# Un_Bus.net
KiCad netlist of a schematic drawn in EAGLE
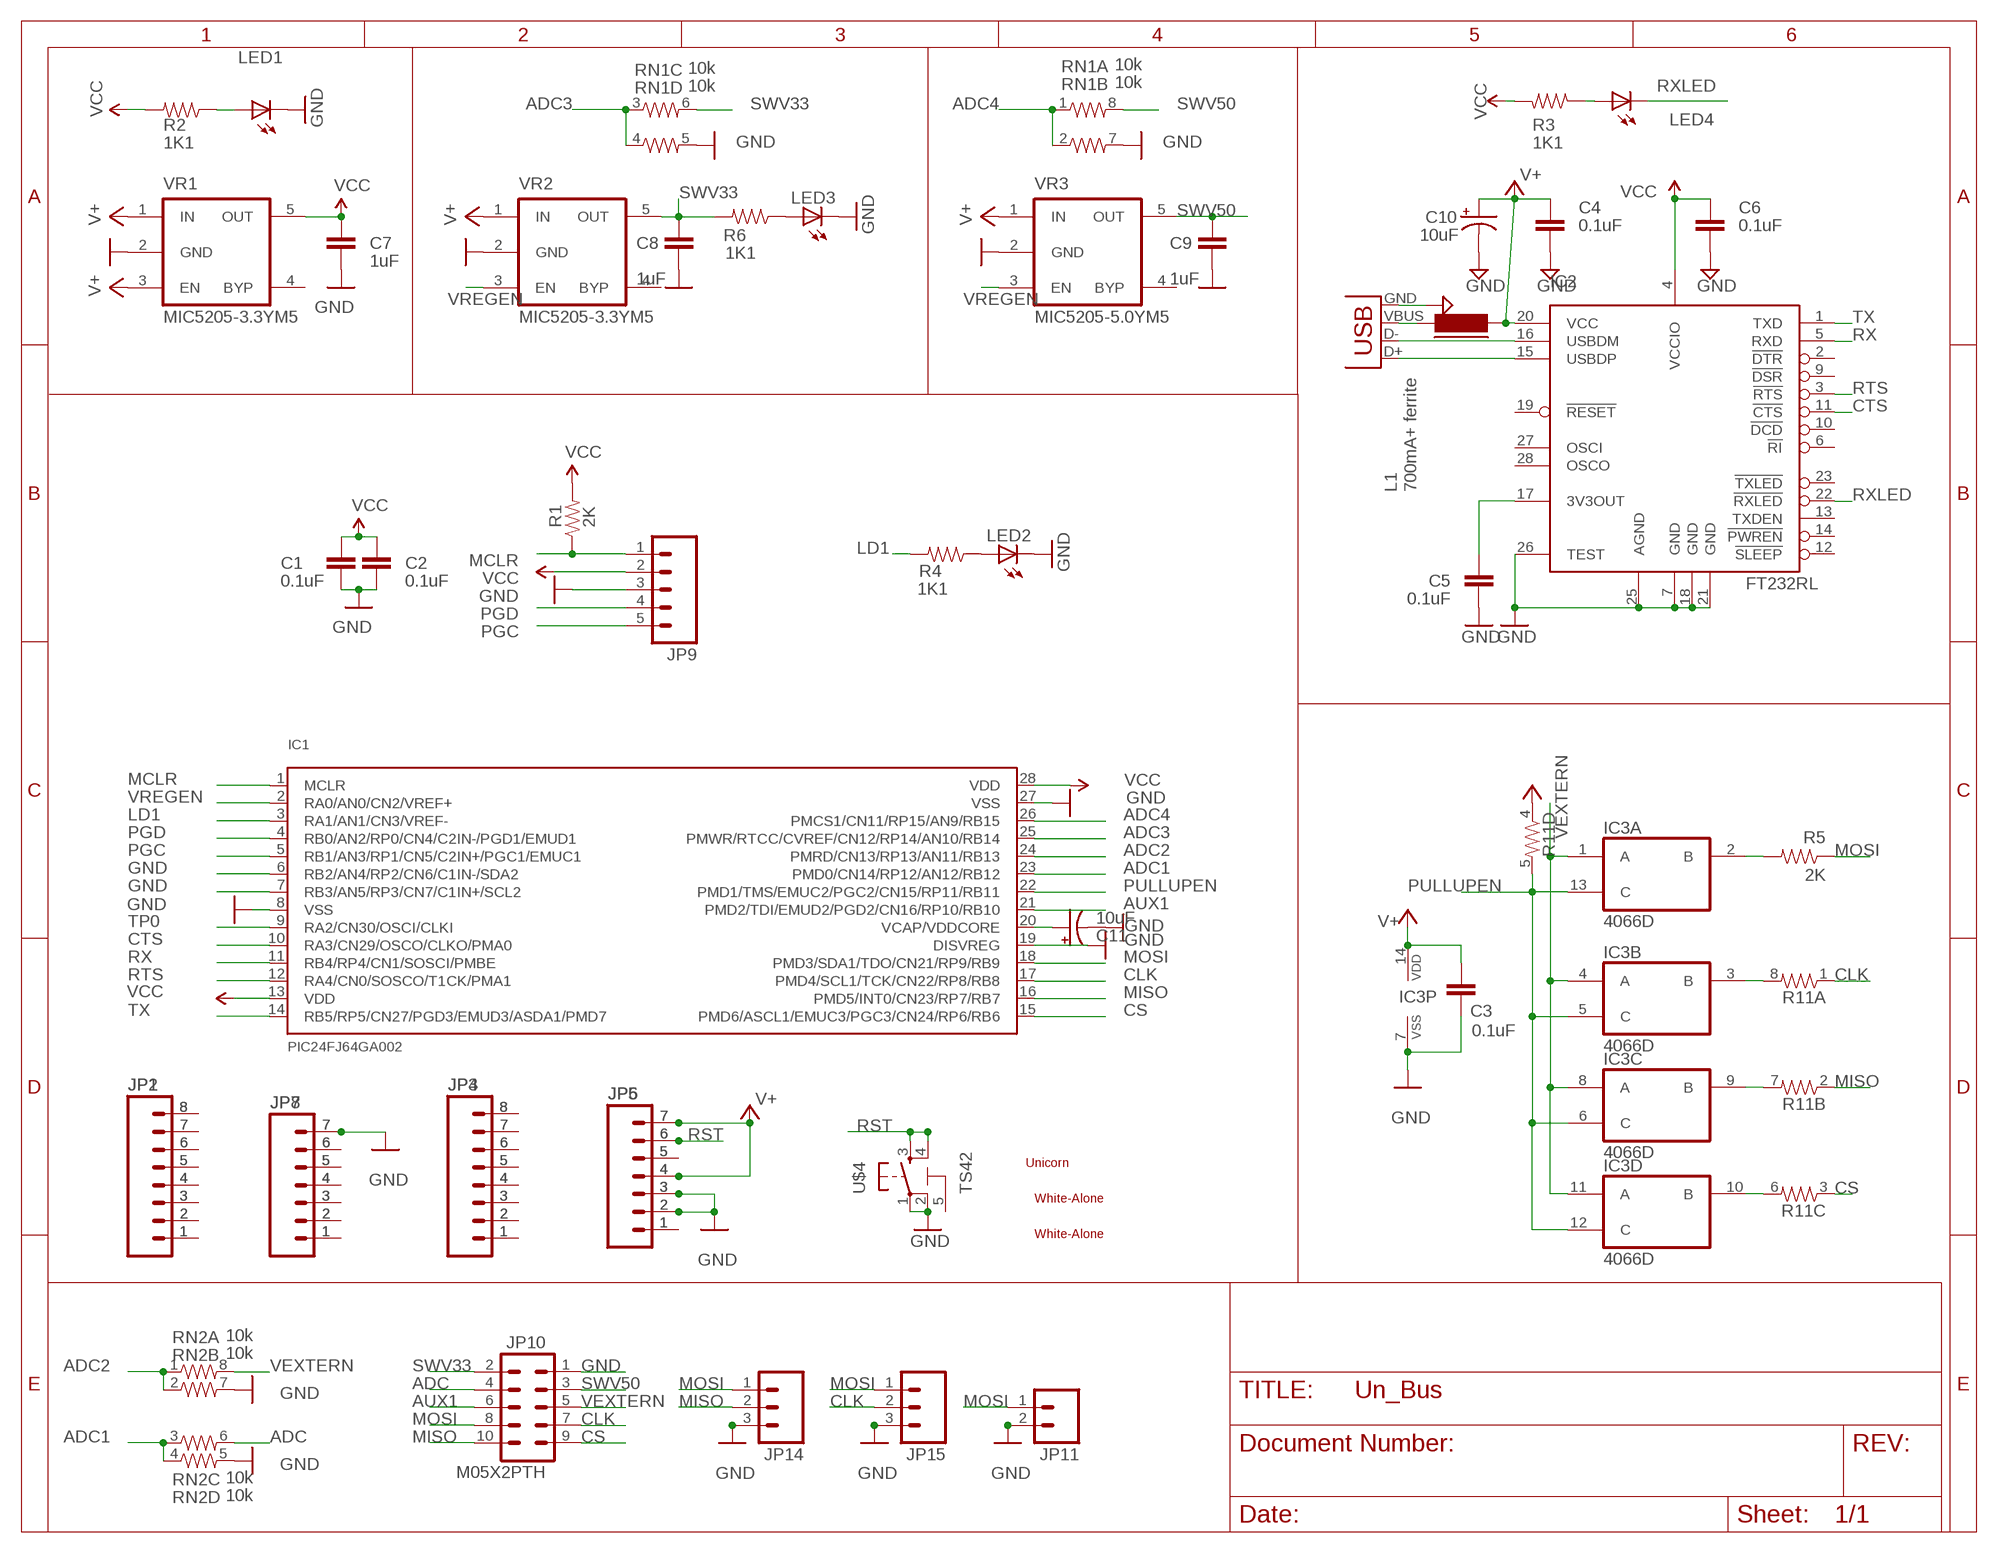
[diagram p0: schematic, sheet 1]

(export (version "E")
  (design (tool "Eeschema 10.0.6"))
  (components
    (comp (ref "C1")
      (value "0.1uF")
      (footprint "eagle-import:0603-CAP")
      (libsource (lib "eagle-import") (part "CAP0603-CAP"))
    )
    (comp (ref "C2")
      (value "0.1uF")
      (footprint "eagle-import:0603-CAP")
      (libsource (lib "eagle-import") (part "CAP0603-CAP"))
    )
    (comp (ref "C3")
      (value "0.1uF")
      (footprint "eagle-import:0603-CAP")
      (libsource (lib "eagle-import") (part "CAP0603-CAP"))
    )
    (comp (ref "C4")
      (value "0.1uF")
      (footprint "eagle-import:0603-CAP")
      (libsource (lib "eagle-import") (part "CAP0603-CAP"))
    )
    (comp (ref "C5")
      (value "0.1uF")
      (footprint "eagle-import:0603-CAP")
      (libsource (lib "eagle-import") (part "CAP0603-CAP"))
    )
    (comp (ref "C6")
      (value "0.1uF")
      (footprint "eagle-import:0603-CAP")
      (libsource (lib "eagle-import") (part "CAP0603-CAP"))
    )
    (comp (ref "C7")
      (value "1uF")
      (footprint "eagle-import:0603-CAP")
      (libsource (lib "eagle-import") (part "CAP0603-CAP"))
    )
    (comp (ref "C8")
      (value "1uF")
      (footprint "eagle-import:0603-CAP")
      (libsource (lib "eagle-import") (part "CAP0603-CAP"))
    )
    (comp (ref "C9")
      (value "1uF")
      (footprint "eagle-import:0603-CAP")
      (libsource (lib "eagle-import") (part "CAP0603-CAP"))
    )
    (comp (ref "C10")
      (value "10uF")
      (footprint "eagle-import:EIA3216")
      (libsource (lib "eagle-import") (part "CAP_POL1206"))
    )
    (comp (ref "C11")
      (value "10uF")
      (footprint "eagle-import:EIA3216")
      (libsource (lib "eagle-import") (part "CAP_POL1206"))
    )
    (comp (ref "IC1")
      (value "PIC24FJ64GA002")
      (footprint "eagle-import:SSOP28")
      (libsource (lib "eagle-import") (part "PIC24FJ64GA002"))
    )
    (comp (ref "IC2")
      (value "FT232RL")
      (footprint "eagle-import:SSOP28")
      (libsource (lib "eagle-import") (part "FT232RL"))
    )
    (comp (ref "IC3")
      (value "4066D")
      (footprint "eagle-import:SO14")
      (libsource (lib "eagle-import") (part "4066D"))
    )
    (comp (ref "JP1")
      (value "M081X08")
      (footprint "eagle-import:1X08")
      (libsource (lib "eagle-import") (part "M081X08"))
    )
    (comp (ref "JP2")
      (value "M081X08")
      (footprint "eagle-import:1X08")
      (libsource (lib "eagle-import") (part "M081X08"))
    )
    (comp (ref "JP3")
      (value "M081X08")
      (footprint "eagle-import:1X08")
      (libsource (lib "eagle-import") (part "M081X08"))
    )
    (comp (ref "JP4")
      (value "M081X08")
      (footprint "eagle-import:1X08")
      (libsource (lib "eagle-import") (part "M081X08"))
    )
    (comp (ref "JP5")
      (value "M07")
      (footprint "eagle-import:1X07")
      (libsource (lib "eagle-import") (part "M07"))
    )
    (comp (ref "JP6")
      (value "M07")
      (footprint "eagle-import:1X07")
      (libsource (lib "eagle-import") (part "M07"))
    )
    (comp (ref "JP7")
      (value "M07")
      (footprint "eagle-import:1X07")
      (libsource (lib "eagle-import") (part "M07"))
    )
    (comp (ref "JP8")
      (value "M07")
      (footprint "eagle-import:1X07")
      (libsource (lib "eagle-import") (part "M07"))
    )
    (comp (ref "JP9")
      (value "M05PTH")
      (footprint "eagle-import:1X05")
      (libsource (lib "eagle-import") (part "M05PTH"))
    )
    (comp (ref "JP10")
      (value "M05X2PTH")
      (footprint "eagle-import:AVR_ICSP")
      (libsource (lib "eagle-import") (part "M05X2PTH"))
    )
    (comp (ref "JP11")
      (value "M02PTH")
      (footprint "eagle-import:1X02")
      (libsource (lib "eagle-import") (part "M02PTH"))
    )
    (comp (ref "JP14")
      (value "M03PTH")
      (footprint "eagle-import:1X03")
      (libsource (lib "eagle-import") (part "M03PTH"))
    )
    (comp (ref "JP15")
      (value "M03PTH")
      (footprint "eagle-import:1X03")
      (libsource (lib "eagle-import") (part "M03PTH"))
    )
    (comp (ref "L1")
      (value "700mA+ ferrite")
      (footprint "eagle-import:FB805")
      (libsource (lib "eagle-import") (part "FERRITE-0805"))
    )
    (comp (ref "LED1")
      (value "LED0805")
      (footprint "eagle-import:LED-0805")
      (libsource (lib "eagle-import") (part "LED0805"))
    )
    (comp (ref "LED2")
      (value "LED0805")
      (footprint "eagle-import:LED-0805")
      (libsource (lib "eagle-import") (part "LED0805"))
    )
    (comp (ref "LED3")
      (value "LED0805")
      (footprint "eagle-import:LED-0805")
      (libsource (lib "eagle-import") (part "LED0805"))
    )
    (comp (ref "LED4")
      (value "LED0805")
      (footprint "eagle-import:LED-0805")
      (libsource (lib "eagle-import") (part "LED0805"))
    )
    (comp (ref "R1")
      (value "2K")
      (footprint "eagle-import:0603-RES")
      (libsource (lib "eagle-import") (part "2SparkFun_RESISTOR0603-RES"))
    )
    (comp (ref "R2")
      (value "1K1")
      (footprint "eagle-import:0603-RES")
      (libsource (lib "eagle-import") (part "RESISTOR0603-RES"))
    )
    (comp (ref "R3")
      (value "1K1")
      (footprint "eagle-import:0603-RES")
      (libsource (lib "eagle-import") (part "RESISTOR0603-RES"))
    )
    (comp (ref "R4")
      (value "1K1")
      (footprint "eagle-import:0603-RES")
      (libsource (lib "eagle-import") (part "RESISTOR0603-RES"))
    )
    (comp (ref "R5")
      (value "2K")
      (footprint "eagle-import:0603-RES")
      (libsource (lib "eagle-import") (part "2SparkFun_RESISTOR0603-RES"))
    )
    (comp (ref "R6")
      (value "1K1")
      (footprint "eagle-import:0603-RES")
      (libsource (lib "eagle-import") (part "RESISTOR0603-RES"))
    )
    (comp (ref "R11")
      (value "RESISTOR-ARRAY")
      (footprint "eagle-import:RES-NET-0603")
      (libsource (lib "eagle-import") (part "RESISTOR-ARRAY"))
    )
    (comp (ref "RN1")
      (value "10k")
      (footprint "eagle-import:RES-NET-0603")
      (libsource (lib "eagle-import") (part "RESISTOR-ARRAY"))
    )
    (comp (ref "RN2")
      (value "10k")
      (footprint "eagle-import:RES-NET-0603")
      (libsource (lib "eagle-import") (part "RESISTOR-ARRAY"))
    )
    (comp (ref "U$1")
      (value "UNICORN")
      (footprint "eagle-import:UNICORN_1")
      (libsource (lib "eagle-import") (part "UNICORN"))
    )
    (comp (ref "U$2")
      (value "WHITE-ALONE_0")
      (footprint "eagle-import:WHITE-ALONE_0")
      (libsource (lib "eagle-import") (part "WHITE-ALONE_0"))
    )
    (comp (ref "U$3")
      (value "WHITE-ALONE_0")
      (footprint "eagle-import:WHITE-ALONE_0")
      (libsource (lib "eagle-import") (part "WHITE-ALONE_0"))
    )
    (comp (ref "U$4")
      (value "TS42")
      (footprint "eagle-import:TS42")
      (libsource (lib "eagle-import") (part "TS42"))
    )
    (comp (ref "VR1")
      (value "MIC5205-3.3YM5")
      (footprint "eagle-import:SOT-23-5")
      (libsource (lib "eagle-import") (part "MIC5205"))
    )
    (comp (ref "VR2")
      (value "MIC5205-3.3YM5")
      (footprint "eagle-import:SOT-23-5")
      (libsource (lib "eagle-import") (part "MIC5205"))
    )
    (comp (ref "VR3")
      (value "MIC5205-5.0YM5")
      (footprint "eagle-import:SOT-23-5")
      (libsource (lib "eagle-import") (part "MIC5205"))
    )
    (comp (ref "X1")
      (value "USBSMD")
      (footprint "eagle-import:USB-MINIB")
      (libsource (lib "eagle-import") (part "USBSMD"))
    )
  )
  (nets
    (net (code "1") (name "/ADC") (class "Default")
      (node (ref "JP10") (pin "4") (pinfunction "4_4") (pintype "passive"))
      (node (ref "RN2") (pin "6") (pinfunction "2_6") (pintype "passive"))
    )
    (net (code "2") (name "/ADC1") (class "Default")
      (node (ref "IC1") (pin "23") (pinfunction "PMD0/CN14/RP12/AN12/RB12_23") (pintype "bidirectional"))
      (node (ref "RN2") (pin "3") (pinfunction "1_3") (pintype "passive"))
      (node (ref "RN2") (pin "4") (pinfunction "1_4") (pintype "passive"))
    )
    (net (code "3") (name "/ADC2") (class "Default")
      (node (ref "IC1") (pin "24") (pinfunction "PMRD/CN13/RP13/AN11/RB13_24") (pintype "bidirectional"))
      (node (ref "RN2") (pin "1") (pinfunction "1_1") (pintype "passive"))
      (node (ref "RN2") (pin "2") (pinfunction "1_2") (pintype "passive"))
    )
    (net (code "4") (name "/ADC3") (class "Default")
      (node (ref "IC1") (pin "25") (pinfunction "PMWR/RTCC/CVREF/CN12/RP14/AN10/RB14_25") (pintype "bidirectional"))
      (node (ref "RN1") (pin "3") (pinfunction "1_3") (pintype "passive"))
      (node (ref "RN1") (pin "4") (pinfunction "1_4") (pintype "passive"))
    )
    (net (code "5") (name "/ADC4") (class "Default")
      (node (ref "IC1") (pin "26") (pinfunction "PMCS1/CN11/RP15/AN9/RB15_26") (pintype "bidirectional"))
      (node (ref "RN1") (pin "1") (pinfunction "1_1") (pintype "passive"))
      (node (ref "RN1") (pin "2") (pinfunction "1_2") (pintype "passive"))
    )
    (net (code "6") (name "/AUX1") (class "Default")
      (node (ref "IC1") (pin "21") (pinfunction "PMD2/TDI/EMUD2/PGD2/CN16/RP10/RB10_21") (pintype "bidirectional"))
      (node (ref "JP10") (pin "6") (pinfunction "6_6") (pintype "passive"))
    )
    (net (code "7") (name "/CLK") (class "Default")
      (node (ref "IC1") (pin "17") (pinfunction "PMD4/SCL1/TCK/CN22/RP8/RB8_17") (pintype "bidirectional"))
      (node (ref "JP10") (pin "7") (pinfunction "7_7") (pintype "passive"))
      (node (ref "JP15") (pin "2") (pinfunction "2_2") (pintype "passive"))
      (node (ref "R11") (pin "1") (pinfunction "1_1") (pintype "passive"))
    )
    (net (code "8") (name "/CS") (class "Default")
      (node (ref "IC1") (pin "15") (pinfunction "PMD6/ASCL1/EMUC3/PGC3/CN24/RP6/RB6_15") (pintype "bidirectional"))
      (node (ref "JP10") (pin "9") (pinfunction "9_9") (pintype "passive"))
      (node (ref "R11") (pin "3") (pinfunction "1_3") (pintype "passive"))
    )
    (net (code "9") (name "/CTS") (class "Default")
      (node (ref "IC1") (pin "10") (pinfunction "RA3/CN29/OSCO/CLKO/PMA0_10") (pintype "bidirectional"))
      (node (ref "IC2") (pin "11") (pinfunction "~{CTS}_11") (pintype "bidirectional"))
    )
    (net (code "10") (name "/LD1") (class "Default")
      (node (ref "IC1") (pin "3") (pinfunction "RA1/AN1/CN3/VREF-_3") (pintype "bidirectional"))
      (node (ref "R4") (pin "2") (pinfunction "2_2") (pintype "passive"))
    )
    (net (code "11") (name "/MCLR") (class "Default")
      (node (ref "IC1") (pin "1") (pinfunction "MCLR_1") (pintype "input"))
      (node (ref "JP9") (pin "1") (pinfunction "1_1") (pintype "passive"))
      (node (ref "R1") (pin "1") (pinfunction "1_1") (pintype "passive"))
    )
    (net (code "12") (name "/MISO") (class "Default")
      (node (ref "IC1") (pin "16") (pinfunction "PMD5/INT0/CN23/RP7/RB7_16") (pintype "bidirectional"))
      (node (ref "JP10") (pin "10") (pinfunction "10_10") (pintype "passive"))
      (node (ref "JP14") (pin "2") (pinfunction "2_2") (pintype "passive"))
      (node (ref "R11") (pin "2") (pinfunction "1_2") (pintype "passive"))
    )
    (net (code "13") (name "/MOSI") (class "Default")
      (node (ref "IC1") (pin "18") (pinfunction "PMD3/SDA1/TDO/CN21/RP9/RB9_18") (pintype "bidirectional"))
      (node (ref "JP10") (pin "8") (pinfunction "8_8") (pintype "passive"))
      (node (ref "JP11") (pin "1") (pinfunction "1_1") (pintype "passive"))
      (node (ref "JP14") (pin "1") (pinfunction "1_1") (pintype "passive"))
      (node (ref "JP15") (pin "1") (pinfunction "1_1") (pintype "passive"))
      (node (ref "R5") (pin "1") (pinfunction "1_1") (pintype "passive"))
    )
    (net (code "14") (name "/PGC") (class "Default")
      (node (ref "IC1") (pin "5") (pinfunction "RB1/AN3/RP1/CN5/C2IN+/PGC1/EMUC1_5") (pintype "bidirectional"))
      (node (ref "JP9") (pin "5") (pinfunction "5_5") (pintype "passive"))
    )
    (net (code "15") (name "/PGD") (class "Default")
      (node (ref "IC1") (pin "4") (pinfunction "RB0/AN2/RP0/CN4/C2IN-/PGD1/EMUD1_4") (pintype "bidirectional"))
      (node (ref "JP9") (pin "4") (pinfunction "4_4") (pintype "passive"))
    )
    (net (code "16") (name "/PULLUPEN") (class "Default")
      (node (ref "IC1") (pin "22") (pinfunction "PMD1/TMS/EMUC2/PGC2/CN15/RP11/RB11_22") (pintype "bidirectional"))
      (node (ref "IC3") (pin "12") (pinfunction "C_12") (pintype "input"))
      (node (ref "IC3") (pin "13") (pinfunction "C_13") (pintype "input"))
      (node (ref "IC3") (pin "5") (pinfunction "C_5") (pintype "input"))
      (node (ref "IC3") (pin "6") (pinfunction "C_6") (pintype "input"))
      (node (ref "R11") (pin "5") (pinfunction "2_5") (pintype "passive"))
    )
    (net (code "17") (name "/RST") (class "Default")
      (node (ref "JP5") (pin "6") (pinfunction "6_6") (pintype "passive"))
      (node (ref "JP6") (pin "6") (pinfunction "6_6") (pintype "passive"))
      (node (ref "U$4") (pin "3") (pinfunction "3_3") (pintype "passive"))
      (node (ref "U$4") (pin "4") (pinfunction "4_4") (pintype "passive"))
    )
    (net (code "18") (name "/RTS") (class "Default")
      (node (ref "IC1") (pin "12") (pinfunction "RA4/CN0/SOSCO/T1CK/PMA1_12") (pintype "bidirectional"))
      (node (ref "IC2") (pin "3") (pinfunction "~{RTS}_3") (pintype "bidirectional"))
    )
    (net (code "19") (name "/RX") (class "Default")
      (node (ref "IC1") (pin "11") (pinfunction "RB4/RP4/CN1/SOSCI/PMBE_11") (pintype "bidirectional"))
      (node (ref "IC2") (pin "5") (pinfunction "RXD_5") (pintype "bidirectional"))
    )
    (net (code "20") (name "/RXLED") (class "Default")
      (node (ref "IC2") (pin "22") (pinfunction "~{RXLED}_22") (pintype "bidirectional"))
      (node (ref "LED4") (pin "2") (pinfunction "C_2") (pintype "passive"))
    )
    (net (code "21") (name "/SWV33") (class "Default")
      (node (ref "C8") (pin "1") (pinfunction "1_1") (pintype "passive"))
      (node (ref "JP10") (pin "2") (pinfunction "2_2") (pintype "passive"))
      (node (ref "R6") (pin "2") (pinfunction "2_2") (pintype "passive"))
      (node (ref "RN1") (pin "6") (pinfunction "2_6") (pintype "passive"))
      (node (ref "VR2") (pin "5") (pinfunction "OUT_5") (pintype "bidirectional"))
    )
    (net (code "22") (name "/SWV50") (class "Default")
      (node (ref "C9") (pin "1") (pinfunction "1_1") (pintype "passive"))
      (node (ref "JP10") (pin "3") (pinfunction "3_3") (pintype "passive"))
      (node (ref "RN1") (pin "8") (pinfunction "2_8") (pintype "passive"))
      (node (ref "VR3") (pin "5") (pinfunction "OUT_5") (pintype "bidirectional"))
    )
    (net (code "23") (name "/TP0") (class "Default")
      (node (ref "IC1") (pin "9") (pinfunction "RA2/CN30/OSCI/CLKI_9") (pintype "bidirectional"))
    )
    (net (code "24") (name "/TX") (class "Default")
      (node (ref "IC1") (pin "14") (pinfunction "RB5/RP5/CN27/PGD3/EMUD3/ASDA1/PMD7_14") (pintype "bidirectional"))
      (node (ref "IC2") (pin "1") (pinfunction "TXD_1") (pintype "bidirectional"))
    )
    (net (code "25") (name "/VEXTERN") (class "Default")
      (node (ref "IC3") (pin "1") (pinfunction "A_1") (pintype "tri_state"))
      (node (ref "IC3") (pin "11") (pinfunction "A_11") (pintype "tri_state"))
      (node (ref "IC3") (pin "4") (pinfunction "A_4") (pintype "tri_state"))
      (node (ref "IC3") (pin "8") (pinfunction "A_8") (pintype "tri_state"))
      (node (ref "JP10") (pin "5") (pinfunction "5_5") (pintype "passive"))
      (node (ref "RN2") (pin "8") (pinfunction "2_8") (pintype "passive"))
    )
    (net (code "26") (name "/VREGEN") (class "Default")
      (node (ref "IC1") (pin "2") (pinfunction "RA0/AN0/CN2/VREF+_2") (pintype "bidirectional"))
      (node (ref "VR2") (pin "3") (pinfunction "EN_3") (pintype "bidirectional"))
      (node (ref "VR3") (pin "3") (pinfunction "EN_3") (pintype "bidirectional"))
    )
    (net (code "27") (name "GND") (class "Default")
      (node (ref "C1") (pin "2") (pinfunction "2_2") (pintype "passive"))
      (node (ref "C10") (pin "C") (pinfunction "-_C") (pintype "passive"))
      (node (ref "C11") (pin "C") (pinfunction "-_C") (pintype "passive"))
      (node (ref "C2") (pin "2") (pinfunction "2_2") (pintype "passive"))
      (node (ref "C3") (pin "2") (pinfunction "2_2") (pintype "passive"))
      (node (ref "C4") (pin "2") (pinfunction "2_2") (pintype "passive"))
      (node (ref "C5") (pin "2") (pinfunction "2_2") (pintype "passive"))
      (node (ref "C6") (pin "2") (pinfunction "2_2") (pintype "passive"))
      (node (ref "C7") (pin "2") (pinfunction "2_2") (pintype "passive"))
      (node (ref "C8") (pin "2") (pinfunction "2_2") (pintype "passive"))
      (node (ref "C9") (pin "2") (pinfunction "2_2") (pintype "passive"))
      (node (ref "IC1") (pin "19") (pinfunction "DISVREG_19") (pintype "power_in"))
      (node (ref "IC1") (pin "27") (pinfunction "VSS_27") (pintype "power_in"))
      (node (ref "IC1") (pin "6") (pinfunction "RB2/AN4/RP2/CN6/C1IN-/SDA2_6") (pintype "bidirectional"))
      (node (ref "IC1") (pin "7") (pinfunction "RB3/AN5/RP3/CN7/C1IN+/SCL2_7") (pintype "bidirectional"))
      (node (ref "IC1") (pin "8") (pinfunction "VSS_8") (pintype "power_in"))
      (node (ref "IC2") (pin "18") (pinfunction "GND_18") (pintype "bidirectional"))
      (node (ref "IC2") (pin "21") (pinfunction "GND_21") (pintype "bidirectional"))
      (node (ref "IC2") (pin "25") (pinfunction "AGND_25") (pintype "bidirectional"))
      (node (ref "IC2") (pin "26") (pinfunction "TEST_26") (pintype "bidirectional"))
      (node (ref "IC2") (pin "7") (pinfunction "GND_7") (pintype "bidirectional"))
      (node (ref "IC3") (pin "7") (pinfunction "VSS_7") (pintype "power_in"))
      (node (ref "JP10") (pin "1") (pinfunction "1_1") (pintype "passive"))
      (node (ref "JP11") (pin "2") (pinfunction "2_2") (pintype "passive"))
      (node (ref "JP14") (pin "3") (pinfunction "3_3") (pintype "passive"))
      (node (ref "JP15") (pin "3") (pinfunction "3_3") (pintype "passive"))
      (node (ref "JP5") (pin "2") (pinfunction "2_2") (pintype "passive"))
      (node (ref "JP5") (pin "3") (pinfunction "3_3") (pintype "passive"))
      (node (ref "JP6") (pin "2") (pinfunction "2_2") (pintype "passive"))
      (node (ref "JP6") (pin "3") (pinfunction "3_3") (pintype "passive"))
      (node (ref "JP7") (pin "7") (pinfunction "7_7") (pintype "passive"))
      (node (ref "JP8") (pin "7") (pinfunction "7_7") (pintype "passive"))
      (node (ref "JP9") (pin "3") (pinfunction "3_3") (pintype "passive"))
      (node (ref "LED1") (pin "2") (pinfunction "C_2") (pintype "passive"))
      (node (ref "LED2") (pin "2") (pinfunction "C_2") (pintype "passive"))
      (node (ref "LED3") (pin "2") (pinfunction "C_2") (pintype "passive"))
      (node (ref "RN1") (pin "5") (pinfunction "2_5") (pintype "passive"))
      (node (ref "RN1") (pin "7") (pinfunction "2_7") (pintype "passive"))
      (node (ref "RN2") (pin "5") (pinfunction "2_5") (pintype "passive"))
      (node (ref "RN2") (pin "7") (pinfunction "2_7") (pintype "passive"))
      (node (ref "U$4") (pin "1") (pinfunction "1_1") (pintype "passive"))
      (node (ref "U$4") (pin "2") (pinfunction "2_2") (pintype "passive"))
      (node (ref "VR1") (pin "2") (pinfunction "GND_2") (pintype "bidirectional"))
      (node (ref "VR2") (pin "2") (pinfunction "GND_2") (pintype "bidirectional"))
      (node (ref "VR3") (pin "2") (pinfunction "GND_2") (pintype "bidirectional"))
      (node (ref "X1") (pin "GND") (pinfunction "GND_GND") (pintype "bidirectional"))
    )
    (net (code "28") (name "Net-(C11-+)") (class "Default")
      (node (ref "C11") (pin "A") (pinfunction "+_A") (pintype "passive"))
      (node (ref "IC1") (pin "20") (pinfunction "VCAP/VDDCORE_20") (pintype "power_in"))
    )
    (net (code "29") (name "Net-(IC2-3V3OUT)") (class "Default")
      (node (ref "C5") (pin "1") (pinfunction "1_1") (pintype "passive"))
      (node (ref "IC2") (pin "17") (pinfunction "3V3OUT_17") (pintype "bidirectional"))
    )
    (net (code "30") (name "Net-(IC2-USBDM)") (class "Default")
      (node (ref "IC2") (pin "16") (pinfunction "USBDM_16") (pintype "bidirectional"))
      (node (ref "X1") (pin "D-") (pinfunction "D-_D-") (pintype "bidirectional"))
    )
    (net (code "31") (name "Net-(IC2-USBDP)") (class "Default")
      (node (ref "IC2") (pin "15") (pinfunction "USBDP_15") (pintype "bidirectional"))
      (node (ref "X1") (pin "D+") (pinfunction "D+_D+") (pintype "bidirectional"))
    )
    (net (code "32") (name "Net-(IC3A-B)") (class "Default")
      (node (ref "IC3") (pin "2") (pinfunction "B_2") (pintype "tri_state"))
      (node (ref "R5") (pin "2") (pinfunction "2_2") (pintype "passive"))
    )
    (net (code "33") (name "Net-(IC3B-B)") (class "Default")
      (node (ref "IC3") (pin "3") (pinfunction "B_3") (pintype "tri_state"))
      (node (ref "R11") (pin "8") (pinfunction "2_8") (pintype "passive"))
    )
    (net (code "34") (name "Net-(IC3C-B)") (class "Default")
      (node (ref "IC3") (pin "9") (pinfunction "B_9") (pintype "tri_state"))
      (node (ref "R11") (pin "7") (pinfunction "2_7") (pintype "passive"))
    )
    (net (code "35") (name "Net-(IC3D-B)") (class "Default")
      (node (ref "IC3") (pin "10") (pinfunction "B_10") (pintype "tri_state"))
      (node (ref "R11") (pin "6") (pinfunction "2_6") (pintype "passive"))
    )
    (net (code "36") (name "Net-(JP1-Pad1)") (class "Default")
      (node (ref "JP1") (pin "1") (pinfunction "1_1") (pintype "passive"))
      (node (ref "JP2") (pin "1") (pinfunction "1_1") (pintype "passive"))
    )
    (net (code "37") (name "Net-(JP1-Pad2)") (class "Default")
      (node (ref "JP1") (pin "2") (pinfunction "2_2") (pintype "passive"))
      (node (ref "JP2") (pin "2") (pinfunction "2_2") (pintype "passive"))
    )
    (net (code "38") (name "Net-(JP1-Pad3)") (class "Default")
      (node (ref "JP1") (pin "3") (pinfunction "3_3") (pintype "passive"))
      (node (ref "JP2") (pin "3") (pinfunction "3_3") (pintype "passive"))
    )
    (net (code "39") (name "Net-(JP1-Pad4)") (class "Default")
      (node (ref "JP1") (pin "4") (pinfunction "4_4") (pintype "passive"))
      (node (ref "JP2") (pin "4") (pinfunction "4_4") (pintype "passive"))
    )
    (net (code "40") (name "Net-(JP1-Pad5)") (class "Default")
      (node (ref "JP1") (pin "5") (pinfunction "5_5") (pintype "passive"))
      (node (ref "JP2") (pin "5") (pinfunction "5_5") (pintype "passive"))
    )
    (net (code "41") (name "Net-(JP1-Pad6)") (class "Default")
      (node (ref "JP1") (pin "6") (pinfunction "6_6") (pintype "passive"))
      (node (ref "JP2") (pin "6") (pinfunction "6_6") (pintype "passive"))
    )
    (net (code "42") (name "Net-(JP1-Pad7)") (class "Default")
      (node (ref "JP1") (pin "7") (pinfunction "7_7") (pintype "passive"))
      (node (ref "JP2") (pin "7") (pinfunction "7_7") (pintype "passive"))
    )
    (net (code "43") (name "Net-(JP1-Pad8)") (class "Default")
      (node (ref "JP1") (pin "8") (pinfunction "8_8") (pintype "passive"))
      (node (ref "JP2") (pin "8") (pinfunction "8_8") (pintype "passive"))
    )
    (net (code "44") (name "Net-(JP3-Pad1)") (class "Default")
      (node (ref "JP3") (pin "1") (pinfunction "1_1") (pintype "passive"))
      (node (ref "JP4") (pin "1") (pinfunction "1_1") (pintype "passive"))
    )
    (net (code "45") (name "Net-(JP3-Pad2)") (class "Default")
      (node (ref "JP3") (pin "2") (pinfunction "2_2") (pintype "passive"))
      (node (ref "JP4") (pin "2") (pinfunction "2_2") (pintype "passive"))
    )
    (net (code "46") (name "Net-(JP3-Pad3)") (class "Default")
      (node (ref "JP3") (pin "3") (pinfunction "3_3") (pintype "passive"))
      (node (ref "JP4") (pin "3") (pinfunction "3_3") (pintype "passive"))
    )
    (net (code "47") (name "Net-(JP3-Pad4)") (class "Default")
      (node (ref "JP3") (pin "4") (pinfunction "4_4") (pintype "passive"))
      (node (ref "JP4") (pin "4") (pinfunction "4_4") (pintype "passive"))
    )
    (net (code "48") (name "Net-(JP3-Pad5)") (class "Default")
      (node (ref "JP3") (pin "5") (pinfunction "5_5") (pintype "passive"))
      (node (ref "JP4") (pin "5") (pinfunction "5_5") (pintype "passive"))
    )
    (net (code "49") (name "Net-(JP3-Pad6)") (class "Default")
      (node (ref "JP3") (pin "6") (pinfunction "6_6") (pintype "passive"))
      (node (ref "JP4") (pin "6") (pinfunction "6_6") (pintype "passive"))
    )
    (net (code "50") (name "Net-(JP3-Pad7)") (class "Default")
      (node (ref "JP3") (pin "7") (pinfunction "7_7") (pintype "passive"))
      (node (ref "JP4") (pin "7") (pinfunction "7_7") (pintype "passive"))
    )
    (net (code "51") (name "Net-(JP3-Pad8)") (class "Default")
      (node (ref "JP3") (pin "8") (pinfunction "8_8") (pintype "passive"))
      (node (ref "JP4") (pin "8") (pinfunction "8_8") (pintype "passive"))
    )
    (net (code "52") (name "Net-(JP5-Pad1)") (class "Default")
      (node (ref "JP5") (pin "1") (pinfunction "1_1") (pintype "passive"))
      (node (ref "JP6") (pin "1") (pinfunction "1_1") (pintype "passive"))
    )
    (net (code "53") (name "Net-(JP5-Pad5)") (class "Default")
      (node (ref "JP5") (pin "5") (pinfunction "5_5") (pintype "passive"))
      (node (ref "JP6") (pin "5") (pinfunction "5_5") (pintype "passive"))
    )
    (net (code "54") (name "Net-(JP7-Pad1)") (class "Default")
      (node (ref "JP7") (pin "1") (pinfunction "1_1") (pintype "passive"))
      (node (ref "JP8") (pin "1") (pinfunction "1_1") (pintype "passive"))
    )
    (net (code "55") (name "Net-(JP7-Pad2)") (class "Default")
      (node (ref "JP7") (pin "2") (pinfunction "2_2") (pintype "passive"))
      (node (ref "JP8") (pin "2") (pinfunction "2_2") (pintype "passive"))
    )
    (net (code "56") (name "Net-(JP7-Pad3)") (class "Default")
      (node (ref "JP7") (pin "3") (pinfunction "3_3") (pintype "passive"))
      (node (ref "JP8") (pin "3") (pinfunction "3_3") (pintype "passive"))
    )
    (net (code "57") (name "Net-(JP7-Pad4)") (class "Default")
      (node (ref "JP7") (pin "4") (pinfunction "4_4") (pintype "passive"))
      (node (ref "JP8") (pin "4") (pinfunction "4_4") (pintype "passive"))
    )
    (net (code "58") (name "Net-(JP7-Pad5)") (class "Default")
      (node (ref "JP7") (pin "5") (pinfunction "5_5") (pintype "passive"))
      (node (ref "JP8") (pin "5") (pinfunction "5_5") (pintype "passive"))
    )
    (net (code "59") (name "Net-(JP7-Pad6)") (class "Default")
      (node (ref "JP7") (pin "6") (pinfunction "6_6") (pintype "passive"))
      (node (ref "JP8") (pin "6") (pinfunction "6_6") (pintype "passive"))
    )
    (net (code "60") (name "Net-(L1-Pad1)") (class "Default")
      (node (ref "L1") (pin "1") (pinfunction "1_1") (pintype "passive"))
      (node (ref "X1") (pin "VBUS") (pinfunction "VBUS_VBUS") (pintype "bidirectional"))
    )
    (net (code "61") (name "Net-(LED1-A)") (class "Default")
      (node (ref "LED1") (pin "1") (pinfunction "A_1") (pintype "passive"))
      (node (ref "R2") (pin "1") (pinfunction "1_1") (pintype "passive"))
    )
    (net (code "62") (name "Net-(LED2-A)") (class "Default")
      (node (ref "LED2") (pin "1") (pinfunction "A_1") (pintype "passive"))
      (node (ref "R4") (pin "1") (pinfunction "1_1") (pintype "passive"))
    )
    (net (code "63") (name "Net-(LED3-A)") (class "Default")
      (node (ref "LED3") (pin "1") (pinfunction "A_1") (pintype "passive"))
      (node (ref "R6") (pin "1") (pinfunction "1_1") (pintype "passive"))
    )
    (net (code "64") (name "Net-(LED4-A)") (class "Default")
      (node (ref "LED4") (pin "1") (pinfunction "A_1") (pintype "passive"))
      (node (ref "R3") (pin "1") (pinfunction "1_1") (pintype "passive"))
    )
    (net (code "65") (name "V+") (class "Default")
      (node (ref "C10") (pin "A") (pinfunction "+_A") (pintype "passive"))
      (node (ref "C3") (pin "1") (pinfunction "1_1") (pintype "passive"))
      (node (ref "C4") (pin "1") (pinfunction "1_1") (pintype "passive"))
      (node (ref "IC2") (pin "20") (pinfunction "VCC_20") (pintype "bidirectional"))
      (node (ref "IC3") (pin "14") (pinfunction "VDD_14") (pintype "power_in"))
      (node (ref "JP5") (pin "4") (pinfunction "4_4") (pintype "passive"))
      (node (ref "JP5") (pin "7") (pinfunction "7_7") (pintype "passive"))
      (node (ref "JP6") (pin "4") (pinfunction "4_4") (pintype "passive"))
      (node (ref "JP6") (pin "7") (pinfunction "7_7") (pintype "passive"))
      (node (ref "L1") (pin "2") (pinfunction "2_2") (pintype "passive"))
      (node (ref "R11") (pin "4") (pinfunction "1_4") (pintype "passive"))
      (node (ref "VR1") (pin "1") (pinfunction "IN_1") (pintype "bidirectional"))
      (node (ref "VR1") (pin "3") (pinfunction "EN_3") (pintype "bidirectional"))
      (node (ref "VR2") (pin "1") (pinfunction "IN_1") (pintype "bidirectional"))
      (node (ref "VR3") (pin "1") (pinfunction "IN_1") (pintype "bidirectional"))
    )
    (net (code "66") (name "VCC") (class "Default")
      (node (ref "C1") (pin "1") (pinfunction "1_1") (pintype "passive"))
      (node (ref "C2") (pin "1") (pinfunction "1_1") (pintype "passive"))
      (node (ref "C6") (pin "1") (pinfunction "1_1") (pintype "passive"))
      (node (ref "C7") (pin "1") (pinfunction "1_1") (pintype "passive"))
      (node (ref "IC1") (pin "13") (pinfunction "VDD_13") (pintype "power_in"))
      (node (ref "IC1") (pin "28") (pinfunction "VDD_28") (pintype "power_in"))
      (node (ref "IC2") (pin "4") (pinfunction "VCCIO_4") (pintype "bidirectional"))
      (node (ref "JP9") (pin "2") (pinfunction "2_2") (pintype "passive"))
      (node (ref "R1") (pin "2") (pinfunction "2_2") (pintype "passive"))
      (node (ref "R2") (pin "2") (pinfunction "2_2") (pintype "passive"))
      (node (ref "R3") (pin "2") (pinfunction "2_2") (pintype "passive"))
      (node (ref "VR1") (pin "5") (pinfunction "OUT_5") (pintype "bidirectional"))
    )
    (net (code "67") (name "unconnected-(IC2-OSCI-Pad27)") (class "Default")
      (node (ref "IC2") (pin "27") (pinfunction "OSCI_27") (pintype "bidirectional"))
    )
    (net (code "68") (name "unconnected-(IC2-OSCO-Pad28)") (class "Default")
      (node (ref "IC2") (pin "28") (pinfunction "OSCO_28") (pintype "bidirectional"))
    )
    (net (code "69") (name "unconnected-(IC2-TXDEN-Pad13)") (class "Default")
      (node (ref "IC2") (pin "13") (pinfunction "TXDEN_13") (pintype "bidirectional"))
    )
    (net (code "70") (name "unconnected-(IC2-~{DCD}-Pad10)") (class "Default")
      (node (ref "IC2") (pin "10") (pinfunction "~{DCD}_10") (pintype "bidirectional"))
    )
    (net (code "71") (name "unconnected-(IC2-~{DSR}-Pad9)") (class "Default")
      (node (ref "IC2") (pin "9") (pinfunction "~{DSR}_9") (pintype "bidirectional"))
    )
    (net (code "72") (name "unconnected-(IC2-~{DTR}-Pad2)") (class "Default")
      (node (ref "IC2") (pin "2") (pinfunction "~{DTR}_2") (pintype "bidirectional"))
    )
    (net (code "73") (name "unconnected-(IC2-~{PWREN}-Pad14)") (class "Default")
      (node (ref "IC2") (pin "14") (pinfunction "~{PWREN}_14") (pintype "bidirectional"))
    )
    (net (code "74") (name "unconnected-(IC2-~{RESET}-Pad19)") (class "Default")
      (node (ref "IC2") (pin "19") (pinfunction "~{RESET}_19") (pintype "bidirectional"))
    )
    (net (code "75") (name "unconnected-(IC2-~{RI}-Pad6)") (class "Default")
      (node (ref "IC2") (pin "6") (pinfunction "~{RI}_6") (pintype "bidirectional"))
    )
    (net (code "76") (name "unconnected-(IC2-~{SLEEP}-Pad12)") (class "Default")
      (node (ref "IC2") (pin "12") (pinfunction "~{SLEEP}_12") (pintype "bidirectional"))
    )
    (net (code "77") (name "unconnected-(IC2-~{TXLED}-Pad23)") (class "Default")
      (node (ref "IC2") (pin "23") (pinfunction "~{TXLED}_23") (pintype "bidirectional"))
    )
    (net (code "78") (name "unconnected-(U$4-Pad5)") (class "Default")
      (node (ref "U$4") (pin "5") (pinfunction "5_5") (pintype "passive"))
    )
    (net (code "79") (name "unconnected-(VR1-BYP-Pad4)") (class "Default")
      (node (ref "VR1") (pin "4") (pinfunction "BYP_4") (pintype "bidirectional"))
    )
    (net (code "80") (name "unconnected-(VR2-BYP-Pad4)") (class "Default")
      (node (ref "VR2") (pin "4") (pinfunction "BYP_4") (pintype "bidirectional"))
    )
    (net (code "81") (name "unconnected-(VR3-BYP-Pad4)") (class "Default")
      (node (ref "VR3") (pin "4") (pinfunction "BYP_4") (pintype "bidirectional"))
    )
  )
)
